# NNLightSwitcher_QSPI_Flash.net
KiCad netlist of a schematic drawn in Altium Designer
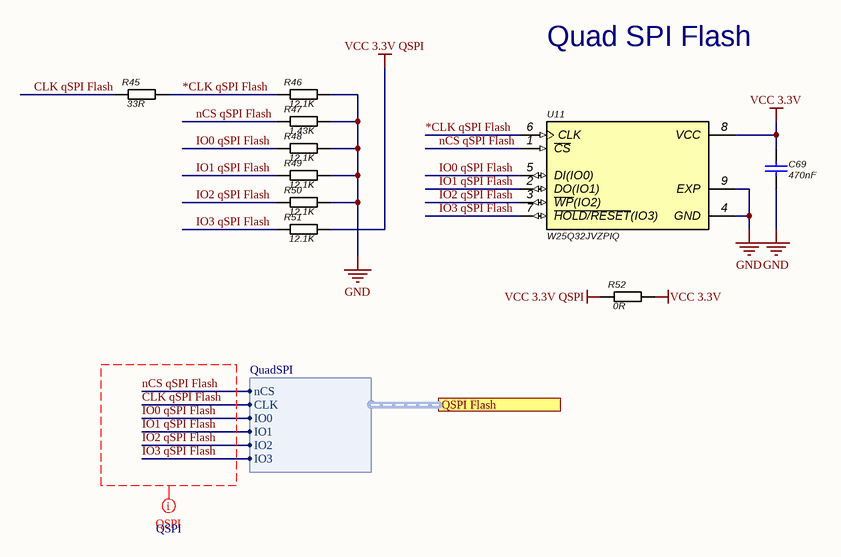
[diagram p0: NNLightSwitcher_QSPI_Flash.SchDoc]

(export (version "E")
  (design (tool "Eeschema 10.0.6"))
  (components
    (comp (ref "C69")
      (value "470nF")
      (footprint "0402")
      (libsource (lib "NNLightSwitcher") (part "Capacitor 470nF"))
    )
    (comp (ref "R45")
      (value "33R")
      (footprint "0402")
      (libsource (lib "NNLightSwitcher") (part "Resistor 33R"))
    )
    (comp (ref "R46")
      (value "12.1K")
      (footprint "0402")
      (libsource (lib "NNLightSwitcher") (part "Resistor 12.1K"))
    )
    (comp (ref "R47")
      (value "1.43K")
      (footprint "0402")
      (libsource (lib "NNLightSwitcher") (part "Resistor 1.43K"))
    )
    (comp (ref "R48")
      (value "12.1K")
      (footprint "0402")
      (libsource (lib "NNLightSwitcher") (part "Resistor 12.1K"))
    )
    (comp (ref "R49")
      (value "12.1K")
      (footprint "0402")
      (libsource (lib "NNLightSwitcher") (part "Resistor 12.1K"))
    )
    (comp (ref "R50")
      (value "12.1K")
      (footprint "0402")
      (libsource (lib "NNLightSwitcher") (part "Resistor 12.1K"))
    )
    (comp (ref "R51")
      (value "12.1K")
      (footprint "0402")
      (libsource (lib "NNLightSwitcher") (part "Resistor 12.1K"))
    )
    (comp (ref "R52")
      (value "0R")
      (footprint "0402")
      (libsource (lib "NNLightSwitcher") (part "Resistor 0R"))
    )
    (comp (ref "U11")
      (value "W25Q32JVZPIQ")
      (footprint "*SON127P600X500X80-9N")
      (description "Serial Flash Memory With Dual, Quad Spi")
      (libsource (lib "NNLightSwitcher") (part "W25Q32JVZPIQ"))
    )
  )
  (nets
    (net (code "2") (name "/*CLK qSPI Flash") (class "Default")
      (node (ref "R45") (pin "2") (pinfunction "2_2") (pintype "passive"))
      (node (ref "R46") (pin "1") (pinfunction "1_1") (pintype "passive"))
      (node (ref "U11") (pin "6") (pinfunction "CLK_6") (pintype "input"))
    )
    (net (code "3") (name "/CLK qSPI Flash") (class "Default")
      (node (ref "R45") (pin "1") (pinfunction "1_1") (pintype "passive"))
    )
    (net (code "4") (name "/IO0 qSPI Flash") (class "Default")
      (node (ref "R48") (pin "1") (pinfunction "1_1") (pintype "passive"))
      (node (ref "U11") (pin "5") (pinfunction "DI(IO0)_5") (pintype "bidirectional"))
    )
    (net (code "5") (name "/IO1 qSPI Flash") (class "Default")
      (node (ref "R49") (pin "1") (pinfunction "1_1") (pintype "passive"))
      (node (ref "U11") (pin "2") (pinfunction "DO(IO1)_2") (pintype "bidirectional"))
    )
    (net (code "6") (name "/IO2 qSPI Flash") (class "Default")
      (node (ref "R50") (pin "1") (pinfunction "1_1") (pintype "passive"))
      (node (ref "U11") (pin "3") (pinfunction "~{WP}(IO2)_3") (pintype "bidirectional"))
    )
    (net (code "7") (name "/IO3 qSPI Flash") (class "Default")
      (node (ref "R51") (pin "1") (pinfunction "1_1") (pintype "passive"))
      (node (ref "U11") (pin "7") (pinfunction "~{HOLD/RESET}(IO3)_7") (pintype "bidirectional"))
    )
    (net (code "8") (name "/nCS qSPI Flash") (class "Default")
      (node (ref "R47") (pin "1") (pinfunction "1_1") (pintype "passive"))
      (node (ref "U11") (pin "1") (pinfunction "~{CS}_1") (pintype "input"))
    )
    (net (code "10") (name "GND") (class "Default")
      (node (ref "C69") (pin "2") (pinfunction "2_2") (pintype "passive"))
      (node (ref "R46") (pin "2") (pinfunction "2_2") (pintype "passive"))
      (node (ref "R47") (pin "2") (pinfunction "2_2") (pintype "passive"))
      (node (ref "R48") (pin "2") (pinfunction "2_2") (pintype "passive"))
      (node (ref "R49") (pin "2") (pinfunction "2_2") (pintype "passive"))
      (node (ref "R50") (pin "2") (pinfunction "2_2") (pintype "passive"))
      (node (ref "U11") (pin "4") (pinfunction "GND_4") (pintype "power_in"))
      (node (ref "U11") (pin "9") (pinfunction "EXP_9") (pintype "passive"))
    )
    (net (code "11") (name "VCC 3.3V") (class "Default")
      (node (ref "C69") (pin "1") (pinfunction "1_1") (pintype "passive"))
      (node (ref "R52") (pin "2") (pinfunction "2_2") (pintype "passive"))
      (node (ref "U11") (pin "8") (pinfunction "VCC_8") (pintype "power_in"))
    )
    (net (code "12") (name "VCC 3.3V QSPI") (class "Default")
      (node (ref "R51") (pin "2") (pinfunction "2_2") (pintype "passive"))
      (node (ref "R52") (pin "1") (pinfunction "1_1") (pintype "passive"))
    )
  )
)
